# Sheet1.net
KiCad netlist of a schematic drawn in Altium Designer
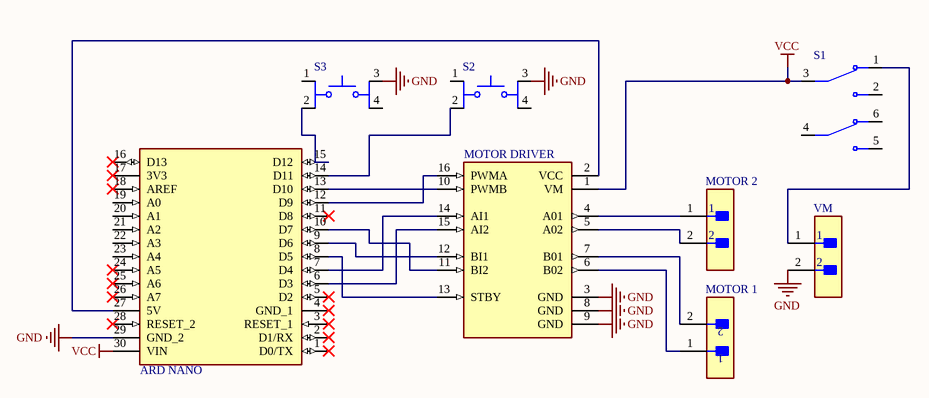
[diagram p0: Sheet1.SchDoc]

(export (version "E")
  (design (tool "Eeschema 10.0.6"))
  (components
    (comp (ref "ARD NANO")
      (value "A000005")
      (footprint "MODULE_A000005")
      (description "Arduino Nano Mikrodenetleyici KartÄ±, ATmega328 ¦ Arduino A000005")
      (fields (field (name "MF") "Arduino"))
      (libsource (lib "A000005") (part "A000005"))
    )
    (comp (ref "MOTOR 1")
      (value "TSW-102-12-T-S")
      (footprint "FP-TSW-102-12-T-S-MFG")
      (description "CONN HEADER VERT 2POS 2.54MM")
      (libsource (lib "") (part "3bc925449376181038e59eaffc5286c_1"))
    )
    (comp (ref "MOTOR 2")
      (value "TSW-102-12-T-S")
      (footprint "FP-TSW-102-12-T-S-MFG")
      (description "CONN HEADER VERT 2POS 2.54MM")
      (libsource (lib "Altium Content Vault") (part "3bc925449376181038e59eaffc5286c"))
    )
    (comp (ref "MOTOR DRIVER")
      (value "~")
      (footprint "MODULE_ROB-14450")
      (description "TB6612FNG Motor Controller/Driver Power Management Evaluation Board")
      (fields (field (name "MP") "ROB-14450") (field (name "MF") "SparkFun Electronics"))
      (libsource (lib "ROB-14450") (part "ROB-14450"))
    )
    (comp (ref "S1")
      (value "TL2285OA")
      (footprint "SW_TL2285OA")
      (description "Pushbutton Switch, TL2285, DPDT, ON-(ON), Plunger for Cap, 100mA, 30VDC,PC Pin ¦ E-Switch TL2285OA")
      (fields (field (name "MF") "E-Switch"))
      (libsource (lib "TL2285OA") (part "TL2285OA"))
    )
    (comp (ref "S2")
      (value "TL1105AF160Q")
      (footprint "SW_TL1105AF160Q")
      (description "Tactile Switch SPST-NO Top Actuated Through Hole")
      (fields (field (name "MF") "E-Switch"))
      (libsource (lib "TL1105AF160Q") (part "TL1105AF160Q"))
    )
    (comp (ref "S3")
      (value "TL1105AF160Q")
      (footprint "SW_TL1105AF160Q")
      (description "Tactile Switch SPST-NO Top Actuated Through Hole")
      (fields (field (name "MF") "E-Switch"))
      (libsource (lib "TL1105AF160Q") (part "TL1105AF160Q"))
    )
    (comp (ref "VM")
      (value "TSW-102-12-T-S")
      (footprint "FP-TSW-102-12-T-S-MFG")
      (description "CONN HEADER VERT 2POS 2.54MM")
      (libsource (lib "Altium Content Vault") (part "3bc925449376181038e59eaffc5286c"))
    )
  )
  (nets
    (net (code "1") (name "GND") (class "Default")
      (node (ref "ARD NANO") (pin "29") (pinfunction "GND_2_29") (pintype "power_in"))
      (node (ref "MOTOR DRIVER") (pin "3") (pinfunction "GND_3") (pintype "power_in"))
      (node (ref "MOTOR DRIVER") (pin "8") (pinfunction "GND_8") (pintype "power_in"))
      (node (ref "MOTOR DRIVER") (pin "9") (pinfunction "GND_9") (pintype "power_in"))
      (node (ref "S2") (pin "3") (pinfunction "3_3") (pintype "passive"))
      (node (ref "S3") (pin "3") (pinfunction "3_3") (pintype "passive"))
      (node (ref "VM") (pin "2") (pinfunction "2_2") (pintype "passive"))
    )
    (net (code "2") (name "Net-(ARD NANO-5V)") (class "Default")
      (node (ref "ARD NANO") (pin "27") (pinfunction "5V_27") (pintype "power_in"))
      (node (ref "MOTOR DRIVER") (pin "2") (pinfunction "VCC_2") (pintype "power_in"))
    )
    (net (code "3") (name "Net-(ARD NANO-D3)") (class "Default")
      (node (ref "ARD NANO") (pin "6") (pinfunction "D3_6") (pintype "bidirectional"))
      (node (ref "MOTOR DRIVER") (pin "15") (pinfunction "AI2_15") (pintype "input"))
    )
    (net (code "4") (name "Net-(ARD NANO-D4)") (class "Default")
      (node (ref "ARD NANO") (pin "7") (pinfunction "D4_7") (pintype "bidirectional"))
      (node (ref "MOTOR DRIVER") (pin "14") (pinfunction "AI1_14") (pintype "input"))
    )
    (net (code "5") (name "Net-(ARD NANO-D5)") (class "Default")
      (node (ref "ARD NANO") (pin "8") (pinfunction "D5_8") (pintype "bidirectional"))
      (node (ref "MOTOR DRIVER") (pin "13") (pinfunction "STBY_13") (pintype "input"))
    )
    (net (code "6") (name "Net-(ARD NANO-D6)") (class "Default")
      (node (ref "ARD NANO") (pin "9") (pinfunction "D6_9") (pintype "bidirectional"))
      (node (ref "MOTOR DRIVER") (pin "12") (pinfunction "BI1_12") (pintype "input"))
    )
    (net (code "7") (name "Net-(ARD NANO-D7)") (class "Default")
      (node (ref "ARD NANO") (pin "10") (pinfunction "D7_10") (pintype "bidirectional"))
      (node (ref "MOTOR DRIVER") (pin "11") (pinfunction "BI2_11") (pintype "input"))
    )
    (net (code "8") (name "Net-(ARD NANO-D9)") (class "Default")
      (node (ref "ARD NANO") (pin "12") (pinfunction "D9_12") (pintype "bidirectional"))
      (node (ref "MOTOR DRIVER") (pin "16") (pinfunction "PWMA_16") (pintype "input"))
    )
    (net (code "9") (name "Net-(ARD NANO-D10)") (class "Default")
      (node (ref "ARD NANO") (pin "13") (pinfunction "D10_13") (pintype "bidirectional"))
      (node (ref "MOTOR DRIVER") (pin "10") (pinfunction "PWMB_10") (pintype "input"))
    )
    (net (code "10") (name "Net-(ARD NANO-D11)") (class "Default")
      (node (ref "ARD NANO") (pin "14") (pinfunction "D11_14") (pintype "bidirectional"))
      (node (ref "S2") (pin "2") (pinfunction "2_2") (pintype "passive"))
    )
    (net (code "11") (name "Net-(ARD NANO-D12)") (class "Default")
      (node (ref "ARD NANO") (pin "15") (pinfunction "D12_15") (pintype "bidirectional"))
      (node (ref "S3") (pin "2") (pinfunction "2_2") (pintype "passive"))
    )
    (net (code "12") (name "Net-(MOTOR DRIVER-A01)") (class "Default")
      (node (ref "MOTOR 2") (pin "1") (pinfunction "1_1") (pintype "passive"))
      (node (ref "MOTOR DRIVER") (pin "4") (pinfunction "A01_4") (pintype "output"))
    )
    (net (code "13") (name "Net-(MOTOR DRIVER-A02)") (class "Default")
      (node (ref "MOTOR 2") (pin "2") (pinfunction "2_2") (pintype "passive"))
      (node (ref "MOTOR DRIVER") (pin "5") (pinfunction "A02_5") (pintype "output"))
    )
    (net (code "14") (name "Net-(MOTOR DRIVER-B01)") (class "Default")
      (node (ref "MOTOR 1") (pin "2") (pinfunction "2_2") (pintype "passive"))
      (node (ref "MOTOR DRIVER") (pin "7") (pinfunction "B01_7") (pintype "output"))
    )
    (net (code "15") (name "Net-(MOTOR DRIVER-B02)") (class "Default")
      (node (ref "MOTOR 1") (pin "1") (pinfunction "1_1") (pintype "passive"))
      (node (ref "MOTOR DRIVER") (pin "6") (pinfunction "B02_6") (pintype "output"))
    )
    (net (code "16") (name "Net-(S1-NC1)") (class "Default")
      (node (ref "S1") (pin "1") (pinfunction "NC1_1") (pintype "passive"))
      (node (ref "VM") (pin "1") (pinfunction "1_1") (pintype "passive"))
    )
    (net (code "17") (name "VCC") (class "Default")
      (node (ref "ARD NANO") (pin "30") (pinfunction "VIN_30") (pintype "power_in"))
      (node (ref "MOTOR DRIVER") (pin "1") (pinfunction "VM_1") (pintype "power_in"))
      (node (ref "S1") (pin "3") (pinfunction "COM1_3") (pintype "passive"))
    )
    (net (code "18") (name "unconnected-(ARD NANO-3V3-Pad17)") (class "Default")
      (node (ref "ARD NANO") (pin "17") (pinfunction "3V3_17") (pintype "power_in+no_connect"))
    )
    (net (code "19") (name "unconnected-(ARD NANO-A0-Pad19)") (class "Default")
      (node (ref "ARD NANO") (pin "19") (pinfunction "A0_19") (pintype "input"))
    )
    (net (code "20") (name "unconnected-(ARD NANO-A1-Pad20)") (class "Default")
      (node (ref "ARD NANO") (pin "20") (pinfunction "A1_20") (pintype "input"))
    )
    (net (code "21") (name "unconnected-(ARD NANO-A2-Pad21)") (class "Default")
      (node (ref "ARD NANO") (pin "21") (pinfunction "A2_21") (pintype "input"))
    )
    (net (code "22") (name "unconnected-(ARD NANO-A3-Pad22)") (class "Default")
      (node (ref "ARD NANO") (pin "22") (pinfunction "A3_22") (pintype "input"))
    )
    (net (code "23") (name "unconnected-(ARD NANO-A4-Pad23)") (class "Default")
      (node (ref "ARD NANO") (pin "23") (pinfunction "A4_23") (pintype "input"))
    )
    (net (code "24") (name "unconnected-(ARD NANO-A5-Pad24)") (class "Default")
      (node (ref "ARD NANO") (pin "24") (pinfunction "A5_24") (pintype "input+no_connect"))
    )
    (net (code "25") (name "unconnected-(ARD NANO-A6-Pad25)") (class "Default")
      (node (ref "ARD NANO") (pin "25") (pinfunction "A6_25") (pintype "input+no_connect"))
    )
    (net (code "26") (name "unconnected-(ARD NANO-A7-Pad26)") (class "Default")
      (node (ref "ARD NANO") (pin "26") (pinfunction "A7_26") (pintype "input+no_connect"))
    )
    (net (code "27") (name "unconnected-(ARD NANO-AREF-Pad18)") (class "Default")
      (node (ref "ARD NANO") (pin "18") (pinfunction "AREF_18") (pintype "input+no_connect"))
    )
    (net (code "28") (name "unconnected-(ARD NANO-D0{slash}TX-Pad1)") (class "Default")
      (node (ref "ARD NANO") (pin "1") (pinfunction "D0/TX_1") (pintype "bidirectional+no_connect"))
    )
    (net (code "29") (name "unconnected-(ARD NANO-D1{slash}RX-Pad2)") (class "Default")
      (node (ref "ARD NANO") (pin "2") (pinfunction "D1/RX_2") (pintype "bidirectional+no_connect"))
    )
    (net (code "30") (name "unconnected-(ARD NANO-D2-Pad5)") (class "Default")
      (node (ref "ARD NANO") (pin "5") (pinfunction "D2_5") (pintype "bidirectional+no_connect"))
    )
    (net (code "31") (name "unconnected-(ARD NANO-D8-Pad11)") (class "Default")
      (node (ref "ARD NANO") (pin "11") (pinfunction "D8_11") (pintype "bidirectional+no_connect"))
    )
    (net (code "32") (name "unconnected-(ARD NANO-D13-Pad16)") (class "Default")
      (node (ref "ARD NANO") (pin "16") (pinfunction "D13_16") (pintype "bidirectional+no_connect"))
    )
    (net (code "33") (name "unconnected-(ARD NANO-GND_1-Pad4)") (class "Default")
      (node (ref "ARD NANO") (pin "4") (pinfunction "GND_1_4") (pintype "power_in+no_connect"))
    )
    (net (code "34") (name "unconnected-(ARD NANO-RESET_1-Pad3)") (class "Default")
      (node (ref "ARD NANO") (pin "3") (pinfunction "RESET_1_3") (pintype "input+no_connect"))
    )
    (net (code "35") (name "unconnected-(ARD NANO-RESET_2-Pad28)") (class "Default")
      (node (ref "ARD NANO") (pin "28") (pinfunction "RESET_2_28") (pintype "input+no_connect"))
    )
    (net (code "36") (name "unconnected-(S1-COM2-Pad4)") (class "Default")
      (node (ref "S1") (pin "4") (pinfunction "COM2_4") (pintype "passive"))
    )
    (net (code "37") (name "unconnected-(S1-NC2-Pad6)") (class "Default")
      (node (ref "S1") (pin "6") (pinfunction "NC2_6") (pintype "passive"))
    )
    (net (code "38") (name "unconnected-(S1-NO1-Pad2)") (class "Default")
      (node (ref "S1") (pin "2") (pinfunction "NO1_2") (pintype "passive"))
    )
    (net (code "39") (name "unconnected-(S1-NO2-Pad5)") (class "Default")
      (node (ref "S1") (pin "5") (pinfunction "NO2_5") (pintype "passive"))
    )
    (net (code "40") (name "unconnected-(S2-Pad1)") (class "Default")
      (node (ref "S2") (pin "1") (pinfunction "1_1") (pintype "passive"))
    )
    (net (code "41") (name "unconnected-(S2-Pad4)") (class "Default")
      (node (ref "S2") (pin "4") (pinfunction "4_4") (pintype "passive"))
    )
    (net (code "42") (name "unconnected-(S3-Pad1)") (class "Default")
      (node (ref "S3") (pin "1") (pinfunction "1_1") (pintype "passive"))
    )
    (net (code "43") (name "unconnected-(S3-Pad4)") (class "Default")
      (node (ref "S3") (pin "4") (pinfunction "4_4") (pintype "passive"))
    )
  )
)
